# RTC.net
KiCad netlist of a schematic drawn in EAGLE
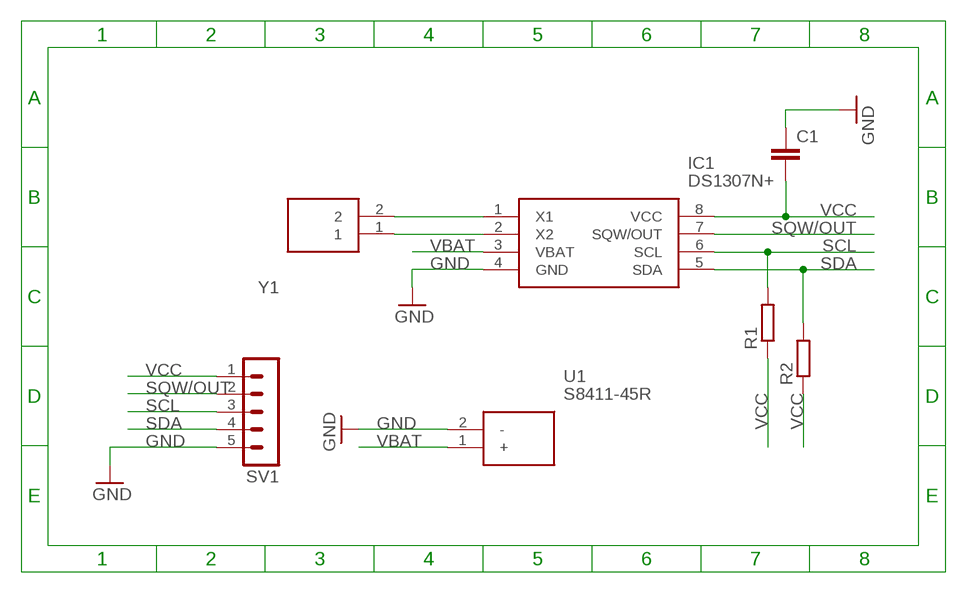
[diagram p0: schematic, sheet 1]

(export (version "E")
  (design (tool "Eeschema 10.0.6"))
  (components
    (comp (ref "C1")
      (value "C-EUC0805")
      (footprint "eagle-import:C0805")
      (libsource (lib "eagle-import") (part "C-EUC0805"))
    )
    (comp (ref "IC1")
      (value "DS1307N+")
      (footprint "eagle-import:DIP762W56P254L938H457Q8N")
      (fields (field (name "MOUSER_PART_NUMBER") "700-DS1307N"))
      (libsource (lib "eagle-import") (part "DS1307N+"))
    )
    (comp (ref "R1")
      (value "R-EU_M1206")
      (footprint "eagle-import:M1206")
      (libsource (lib "eagle-import") (part "R-EU_M1206"))
    )
    (comp (ref "R2")
      (value "R-EU_M1206")
      (footprint "eagle-import:M1206")
      (libsource (lib "eagle-import") (part "R-EU_M1206"))
    )
    (comp (ref "SV1")
      (value "MA05-1")
      (footprint "eagle-import:MA05-1")
      (libsource (lib "eagle-import") (part "MA05-1"))
    )
    (comp (ref "U1")
      (value "S8411-45R")
      (footprint "eagle-import:S8411-45R_1")
      (fields (field (name "MOUSER_PART_NUMBER") "855-S8411-45R"))
      (libsource (lib "eagle-import") (part "S8411-45R"))
    )
    (comp (ref "Y1")
      (value "CM7V-T1A-32.768K-9PF-20PPM-TA-")
      (footprint "eagle-import:CM7VT1A32768KHZ125PF10PPMTBQC")
      (fields
        (field (name "MANUFACTURER_PART_NUMBER") "CM7V-T1A-32.768k-9pF-20PPM-TA-QA T3")
        (field (name "MOUSER_PART_NUMBER") "428-201568-MG03")
      )
      (libsource (lib "eagle-import") (part "CM7V-T1A-32.768K-9PF-20PPM-TA-"))
    )
  )
  (nets
    (net (code "1") (name "/SCL") (class "Default")
      (node (ref "IC1") (pin "6") (pinfunction "SCL_6") (pintype "bidirectional"))
      (node (ref "R1") (pin "2") (pinfunction "2_2") (pintype "passive"))
      (node (ref "SV1") (pin "3") (pinfunction "3_3") (pintype "passive"))
    )
    (net (code "2") (name "/SDA") (class "Default")
      (node (ref "IC1") (pin "5") (pinfunction "SDA_5") (pintype "bidirectional"))
      (node (ref "R2") (pin "2") (pinfunction "2_2") (pintype "passive"))
      (node (ref "SV1") (pin "4") (pinfunction "4_4") (pintype "passive"))
    )
    (net (code "3") (name "/SQW{slash}OUT") (class "Default")
      (node (ref "IC1") (pin "7") (pinfunction "SQW/OUT_7") (pintype "output"))
      (node (ref "SV1") (pin "2") (pinfunction "2_2") (pintype "passive"))
    )
    (net (code "4") (name "/VBAT") (class "Default")
      (node (ref "IC1") (pin "3") (pinfunction "VBAT_3") (pintype "bidirectional"))
      (node (ref "U1") (pin "1") (pinfunction "+_1") (pintype "bidirectional"))
    )
    (net (code "5") (name "/VCC") (class "Default")
      (node (ref "C1") (pin "2") (pinfunction "2_2") (pintype "passive"))
      (node (ref "IC1") (pin "8") (pinfunction "VCC_8") (pintype "power_in"))
      (node (ref "R1") (pin "1") (pinfunction "1_1") (pintype "passive"))
      (node (ref "R2") (pin "1") (pinfunction "1_1") (pintype "passive"))
      (node (ref "SV1") (pin "1") (pinfunction "1_1") (pintype "passive"))
    )
    (net (code "6") (name "GND") (class "Default")
      (node (ref "C1") (pin "1") (pinfunction "1_1") (pintype "passive"))
      (node (ref "IC1") (pin "4") (pinfunction "GND_4") (pintype "power_in"))
      (node (ref "SV1") (pin "5") (pinfunction "5_5") (pintype "passive"))
      (node (ref "U1") (pin "2") (pinfunction "-_2") (pintype "bidirectional"))
    )
    (net (code "7") (name "Net-(IC1-X1)") (class "Default")
      (node (ref "IC1") (pin "1") (pinfunction "X1_1") (pintype "bidirectional"))
      (node (ref "Y1") (pin "2") (pinfunction "2_2") (pintype "bidirectional"))
    )
    (net (code "8") (name "Net-(IC1-X2)") (class "Default")
      (node (ref "IC1") (pin "2") (pinfunction "X2_2") (pintype "bidirectional"))
      (node (ref "Y1") (pin "1") (pinfunction "1_1") (pintype "bidirectional"))
    )
  )
)
